# X-Track_Power.net
KiCad netlist of a schematic drawn in Altium Designer
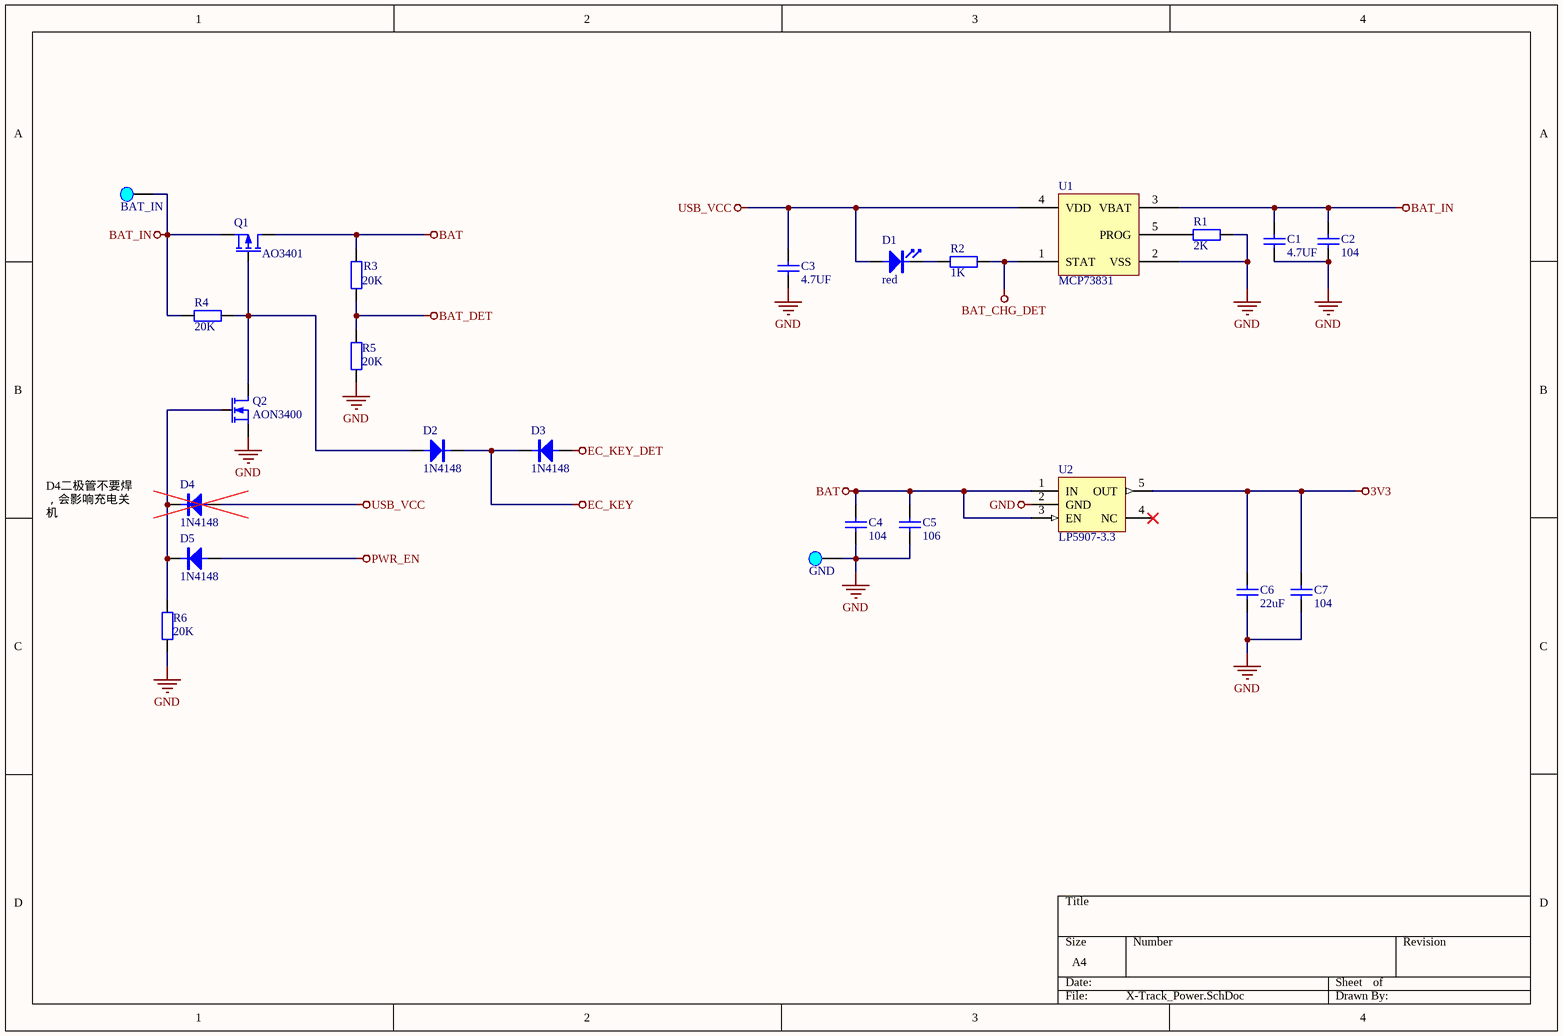
[diagram p0: X-Track_Power.SchDoc]

(export (version "E")
  (design (tool "Eeschema 10.0.6"))
  (components
    (comp (ref "BAT+")
      (value "BAT_IN")
      (footprint "Pad_B")
      (fields (field (name "_REMARKS") "BAT_IN"))
      (libsource (lib "元件库") (part "Pad"))
    )
    (comp (ref "BAT-")
      (value "GND")
      (footprint "Pad_B")
      (fields (field (name "_REMARKS") "GND"))
      (libsource (lib "元件库") (part "Pad"))
    )
    (comp (ref "C1")
      (value "4.7UF")
      (footprint "电容_C0805")
      (fields (field (name "C") "4.7UF"))
      (libsource (lib "元件库") (part "cap"))
    )
    (comp (ref "C2")
      (value "104")
      (footprint "电容_C0603")
      (fields (field (name "C") "104"))
      (libsource (lib "元件库") (part "cap"))
    )
    (comp (ref "C3")
      (value "4.7UF")
      (footprint "电容_C0805")
      (fields (field (name "C") "4.7UF"))
      (libsource (lib "元件库") (part "cap"))
    )
    (comp (ref "C4")
      (value "104")
      (footprint "电容_C0603")
      (fields (field (name "C") "104"))
      (libsource (lib "元件库") (part "cap"))
    )
    (comp (ref "C5")
      (value "106")
      (footprint "电容_C0603")
      (fields (field (name "C") "106"))
      (libsource (lib "元件库") (part "cap"))
    )
    (comp (ref "C6")
      (value "22uF")
      (footprint "电容_C1206")
      (fields (field (name "C") "22uF"))
      (libsource (lib "元件库") (part "cap"))
    )
    (comp (ref "C7")
      (value "104")
      (footprint "电容_C0603")
      (fields (field (name "C") "104"))
      (libsource (lib "元件库") (part "cap"))
    )
    (comp (ref "D1") (value "red") (footprint "LED_0603") (libsource (lib "元件库") (part "LED")))
    (comp (ref "D2")
      (value "1N4148")
      (footprint "二极管_SOD-323")
      (fields (field (name "_MODEL") "1N4148"))
      (libsource (lib "元件库") (part "Diode"))
    )
    (comp (ref "D3")
      (value "1N4148")
      (footprint "二极管_SOD-323")
      (fields (field (name "_MODEL") "1N4148"))
      (libsource (lib "元件库") (part "Diode"))
    )
    (comp (ref "D4")
      (value "1N4148")
      (footprint "二极管_SOD-323")
      (fields (field (name "_MODEL") "1N4148"))
      (libsource (lib "元件库") (part "Diode"))
    )
    (comp (ref "D5")
      (value "1N4148")
      (footprint "二极管_SOD-323")
      (fields (field (name "_MODEL") "1N4148"))
      (libsource (lib "元件库") (part "Diode"))
    )
    (comp (ref "Q1")
      (value "AO3401")
      (footprint "MOS_SOT-23")
      (fields (field (name "_MODEL") "AO3401"))
      (libsource (lib "元件库") (part "MOSFET-P"))
    )
    (comp (ref "Q2")
      (value "AON3400")
      (footprint "MOS_SOT-23")
      (fields (field (name "_MODEL") "AON3400"))
      (libsource (lib "元件库") (part "MOSFET-N"))
    )
    (comp (ref "R1")
      (value "2K")
      (footprint "电阻_R0603")
      (fields (field (name "R") "2K"))
      (libsource (lib "") (part "Res_1"))
    )
    (comp (ref "R2")
      (value "1K")
      (footprint "电阻_R0603")
      (fields (field (name "R") "1K"))
      (libsource (lib "") (part "Res_1"))
    )
    (comp (ref "R3")
      (value "20K")
      (footprint "电阻_R0603")
      (fields (field (name "R") "20K"))
      (libsource (lib "元件库") (part "Res"))
    )
    (comp (ref "R4")
      (value "20K")
      (footprint "电阻_R0603")
      (fields (field (name "R") "20K"))
      (libsource (lib "") (part "Res_3"))
    )
    (comp (ref "R5")
      (value "20K")
      (footprint "电阻_R0603")
      (fields (field (name "R") "20K"))
      (libsource (lib "元件库") (part "Res"))
    )
    (comp (ref "R6")
      (value "20K")
      (footprint "电阻_R0603")
      (fields (field (name "R") "20K"))
      (libsource (lib "") (part "Res_2"))
    )
    (comp (ref "U1")
      (value "MCP73831")
      (footprint "SOT23-5")
      (description "线性充电管理控制器")
      (libsource (lib "TriggersLib") (part "MCP73831"))
    )
    (comp (ref "U2")
      (value "LP5907-3.3")
      (footprint "SOT23-5")
      (description "LDO")
      (libsource (lib "WatchX_TEST") (part "LP5907"))
    )
  )
  (nets
    (net (code "1") (name "3V3") (class "Default")
      (node (ref "C6") (pin "2") (pinfunction "2_2") (pintype "passive"))
      (node (ref "C7") (pin "2") (pinfunction "2_2") (pintype "passive"))
      (node (ref "U2") (pin "5") (pinfunction "OUT_5") (pintype "output"))
    )
    (net (code "2") (name "BAT") (class "Default")
      (node (ref "C4") (pin "2") (pinfunction "2_2") (pintype "passive"))
      (node (ref "C5") (pin "2") (pinfunction "2_2") (pintype "passive"))
      (node (ref "Q1") (pin "2") (pinfunction "D_2") (pintype "passive"))
      (node (ref "R3") (pin "2") (pinfunction "2_2") (pintype "passive"))
      (node (ref "U2") (pin "1") (pinfunction "IN_1") (pintype "power_in"))
      (node (ref "U2") (pin "3") (pinfunction "EN_3") (pintype "input"))
    )
    (net (code "3") (name "BAT_CHG_DET") (class "Default")
      (node (ref "R2") (pin "1") (pinfunction "1_1") (pintype "passive"))
      (node (ref "U1") (pin "1") (pinfunction "STAT_1") (pintype "passive"))
    )
    (net (code "4") (name "BAT_DET") (class "Default")
      (node (ref "R3") (pin "1") (pinfunction "1_1") (pintype "passive"))
      (node (ref "R5") (pin "2") (pinfunction "2_2") (pintype "passive"))
    )
    (net (code "5") (name "BAT_IN") (class "Default")
      (node (ref "BAT+") (pin "1") (pinfunction "*_1") (pintype "passive"))
      (node (ref "C1") (pin "2") (pinfunction "2_2") (pintype "passive"))
      (node (ref "C2") (pin "1") (pinfunction "1_1") (pintype "passive"))
      (node (ref "Q1") (pin "3") (pinfunction "S_3") (pintype "passive"))
      (node (ref "R4") (pin "1") (pinfunction "1_1") (pintype "passive"))
      (node (ref "U1") (pin "3") (pinfunction "VBAT_3") (pintype "passive"))
    )
    (net (code "6") (name "EC_KEY") (class "Default")
      (node (ref "D2") (pin "K") (pinfunction "K_K") (pintype "passive"))
      (node (ref "D3") (pin "K") (pinfunction "K_K") (pintype "passive"))
    )
    (net (code "7") (name "EC_KEY_DET") (class "Default")
      (node (ref "D3") (pin "A") (pinfunction "A_A") (pintype "passive"))
    )
    (net (code "8") (name "GND") (class "Default")
      (node (ref "BAT-") (pin "1") (pinfunction "*_1") (pintype "passive"))
      (node (ref "C1") (pin "1") (pinfunction "1_1") (pintype "passive"))
      (node (ref "C2") (pin "2") (pinfunction "2_2") (pintype "passive"))
      (node (ref "C3") (pin "1") (pinfunction "1_1") (pintype "passive"))
      (node (ref "C4") (pin "1") (pinfunction "1_1") (pintype "passive"))
      (node (ref "C5") (pin "1") (pinfunction "1_1") (pintype "passive"))
      (node (ref "C6") (pin "1") (pinfunction "1_1") (pintype "passive"))
      (node (ref "C7") (pin "1") (pinfunction "1_1") (pintype "passive"))
      (node (ref "Q2") (pin "3") (pinfunction "S_3") (pintype "passive"))
      (node (ref "R1") (pin "1") (pinfunction "1_1") (pintype "passive"))
      (node (ref "R5") (pin "1") (pinfunction "1_1") (pintype "passive"))
      (node (ref "R6") (pin "2") (pinfunction "2_2") (pintype "passive"))
      (node (ref "U1") (pin "2") (pinfunction "VSS_2") (pintype "passive"))
      (node (ref "U2") (pin "2") (pinfunction "GND_2") (pintype "passive"))
    )
    (net (code "9") (name "Net-(D1-PadK)") (class "Default")
      (node (ref "D1") (pin "K") (pinfunction "K_K") (pintype "passive"))
      (node (ref "R2") (pin "2") (pinfunction "2_2") (pintype "passive"))
    )
    (net (code "10") (name "Net-(Q1-G)") (class "Default")
      (node (ref "D2") (pin "A") (pinfunction "A_A") (pintype "passive"))
      (node (ref "Q1") (pin "1") (pinfunction "G_1") (pintype "passive"))
      (node (ref "Q2") (pin "2") (pinfunction "D_2") (pintype "passive"))
      (node (ref "R4") (pin "2") (pinfunction "2_2") (pintype "passive"))
    )
    (net (code "11") (name "Net-(Q2-G)") (class "Default")
      (node (ref "D4") (pin "K") (pinfunction "K_K") (pintype "passive"))
      (node (ref "D5") (pin "K") (pinfunction "K_K") (pintype "passive"))
      (node (ref "Q2") (pin "1") (pinfunction "G_1") (pintype "passive"))
      (node (ref "R6") (pin "1") (pinfunction "1_1") (pintype "passive"))
    )
    (net (code "12") (name "Net-(U1-PROG)") (class "Default")
      (node (ref "R1") (pin "2") (pinfunction "2_2") (pintype "passive"))
      (node (ref "U1") (pin "5") (pinfunction "PROG_5") (pintype "passive"))
    )
    (net (code "13") (name "PWR_EN") (class "Default")
      (node (ref "D5") (pin "A") (pinfunction "A_A") (pintype "passive"))
    )
    (net (code "14") (name "USB_VCC") (class "Default")
      (node (ref "C3") (pin "2") (pinfunction "2_2") (pintype "passive"))
      (node (ref "D1") (pin "A") (pinfunction "A_A") (pintype "passive"))
      (node (ref "D4") (pin "A") (pinfunction "A_A") (pintype "passive"))
      (node (ref "U1") (pin "4") (pinfunction "VDD_4") (pintype "passive"))
    )
    (net (code "15") (name "unconnected-(U2-NC-Pad4)") (class "Default")
      (node (ref "U2") (pin "4") (pinfunction "NC_4") (pintype "passive+no_connect"))
    )
  )
)
